# Power.net
KiCad netlist of a schematic drawn in Altium Designer
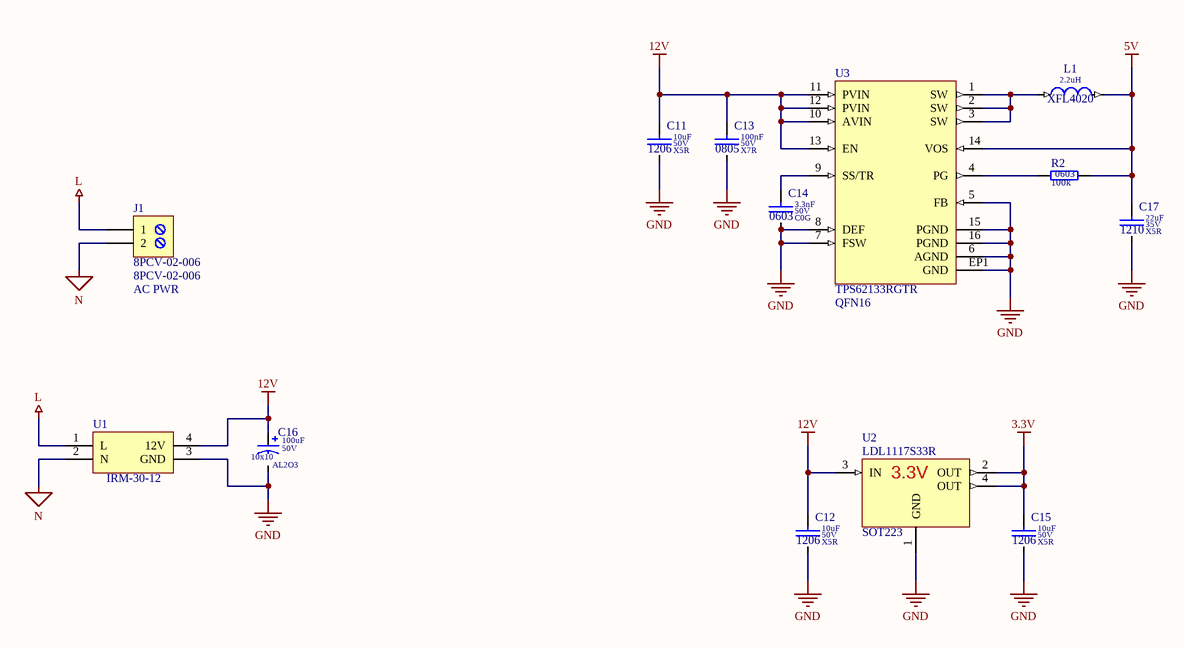
[diagram p0: Power.SchDoc]

(export (version "E")
  (design (tool "Eeschema 10.0.6"))
  (components
    (comp (ref "C11")
      (value "10uF")
      (footprint "C_1206_3216")
      (description "Capacitor")
      (fields
        (field (name "DIELECTRIC") "X5R")
        (field (name "VOLTAGE") "50V")
        (field (name "SCH_FOOTPRINT") "1206")
        (field (name "PART NUMBER") "C_10uF_50V_X5R_1206_10")
        (field (name "MANUFACTURER") "Murata")
      )
      (libsource (lib "Library") (part "C"))
    )
    (comp (ref "C12")
      (value "10uF")
      (footprint "C_1206_3216")
      (description "Capacitor")
      (fields
        (field (name "DIELECTRIC") "X5R")
        (field (name "VOLTAGE") "50V")
        (field (name "SCH_FOOTPRINT") "1206")
        (field (name "PART NUMBER") "C_10uF_50V_X5R_1206_10")
        (field (name "MANUFACTURER") "Murata")
      )
      (libsource (lib "Library") (part "C"))
    )
    (comp (ref "C13")
      (value "100nF")
      (footprint "C_0805_2012")
      (description "Capacitor")
      (fields
        (field (name "DIELECTRIC") "X7R")
        (field (name "VOLTAGE") "50V")
        (field (name "SCH_FOOTPRINT") "0805")
        (field (name "PART NUMBER") "C_100nF_50V_X7R_0805_10")
        (field (name "MANUFACTURER") "AVX")
      )
      (libsource (lib "Library") (part "C"))
    )
    (comp (ref "C14")
      (value "3.3nF")
      (footprint "C_0603_1608")
      (description "Capacitor")
      (fields
        (field (name "DIELECTRIC") "C0G")
        (field (name "VOLTAGE") "50V")
        (field (name "SCH_FOOTPRINT") "0603")
        (field (name "PART NUMBER") "C_3.3nF_50V_C0G_0603_5")
        (field (name "MANUFACTURER") "Murata")
      )
      (libsource (lib "Library") (part "C"))
    )
    (comp (ref "C15")
      (value "10uF")
      (footprint "C_1206_3216")
      (description "Capacitor")
      (fields
        (field (name "DIELECTRIC") "X5R")
        (field (name "VOLTAGE") "50V")
        (field (name "SCH_FOOTPRINT") "1206")
        (field (name "PART NUMBER") "C_10uF_50V_X5R_1206_10")
        (field (name "MANUFACTURER") "Murata")
      )
      (libsource (lib "Library") (part "C"))
    )
    (comp (ref "C16")
      (value "100uF")
      (footprint "CE_D_10x10_SMD")
      (description "Polarized Capacitor")
      (fields
        (field (name "DIELECTRIC") "AL2O3")
        (field (name "SCH_FOOTPRINT") "10x10")
        (field (name "VOLTAGE") "50V")
        (field (name "PART NUMBER") "CE_100uF_50V_AL2O3_10x10_20")
        (field (name "MANUFACTURER") "Nichicon")
      )
      (libsource (lib "Library") (part "CE"))
    )
    (comp (ref "C17")
      (value "22uF")
      (footprint "C_1210_3225")
      (description "Capacitor")
      (fields
        (field (name "DIELECTRIC") "X5R")
        (field (name "VOLTAGE") "35V")
        (field (name "SCH_FOOTPRINT") "1210")
        (field (name "PART NUMBER") "C_22uF_35V_X5R_1210_20")
        (field (name "MANUFACTURER") "Taiyo Yuden")
      )
      (libsource (lib "Library") (part "C"))
    )
    (comp (ref "J1")
      (value "8PCV-02-006")
      (footprint "J_8PCV-02-006")
      (description "ARK Screw terminal, 2-Pin")
      (fields
        (field (name "SCH_FOOTPRINT") "8PCV-02-006")
        (field (name "PART NUMBER") "J_8PCV-02-006")
        (field (name "MANUFACTURER") "TE Connectivity")
      )
      (libsource (lib "Library") (part "J_ARK2"))
    )
    (comp (ref "L1")
      (value "2.2uH")
      (footprint "XFL4020")
      (description "Induction")
      (fields
        (field (name "SCH_FOOTPRINT") "XFL4020")
        (field (name "PART NUMBER") "L_2.2uH_8A_XFL4020")
        (field (name "MANUFACTURER") "Coilcraft")
      )
      (libsource (lib "Library") (part "L"))
    )
    (comp (ref "R2")
      (value "100k")
      (footprint "R_0603_1608")
      (fields
        (field (name "SCH_FOOTPRINT") "0603")
        (field (name "PART NUMBER") "R_100k_0603_1")
        (field (name "VOLTAGE") "50V")
        (field (name "POWER") "100mW")
      )
      (libsource (lib "Library") (part "R"))
    )
    (comp (ref "U1")
      (value "IRM-30-12")
      (footprint "IRM-30-12")
      (description "IRM-30-12 Mean Well")
      (libsource (lib "SchLib") (part "IRM-30-12"))
    )
    (comp (ref "U2")
      (value "LDL1117S33R")
      (footprint "SOT223_SC73")
      (description "typical configuration")
      (fields
        (field (name "SCH_FOOTPRINT") "SOT223")
        (field (name "PART NUMBER") "VL_LDL1117S33R")
        (field (name "VOLTAGE") "3.3V")
      )
      (libsource (lib "Library") (part "VL_4pin_3_1_2,4"))
    )
    (comp (ref "U3")
      (value "TPS62133RGTR")
      (footprint "QFN16_3x3")
      (description "3-17V 3A Step-Down Converter with DCS-Control in 3x3 QFN")
      (fields
        (field (name "SCH_FOOTPRINT") "QFN16")
        (field (name "PART NUMBER") "VS_TPS62133RGTR")
        (field (name "MANUFACTURER") "Texas Instruments")
      )
      (libsource (lib "Library") (part "VS_TPS6213x"))
    )
  )
  (nets
    (net (code "1") (name "3.3V") (class "Default")
      (node (ref "C15") (pin "1") (pinfunction "1_1") (pintype "passive"))
      (node (ref "U2") (pin "2") (pinfunction "OUT_2") (pintype "output"))
      (node (ref "U2") (pin "4") (pinfunction "OUT_4") (pintype "output"))
    )
    (net (code "2") (name "5V") (class "Default")
      (node (ref "C17") (pin "1") (pinfunction "1_1") (pintype "passive"))
      (node (ref "L1") (pin "2") (pinfunction "2_2") (pintype "output"))
      (node (ref "R2") (pin "2") (pinfunction "2_2") (pintype "passive"))
      (node (ref "U3") (pin "14") (pinfunction "VOS_14") (pintype "input"))
    )
    (net (code "3") (name "12V") (class "Default")
      (node (ref "C11") (pin "1") (pinfunction "1_1") (pintype "passive"))
      (node (ref "C12") (pin "1") (pinfunction "1_1") (pintype "passive"))
      (node (ref "C13") (pin "1") (pinfunction "1_1") (pintype "passive"))
      (node (ref "C16") (pin "1") (pinfunction "1_1") (pintype "passive"))
      (node (ref "U1") (pin "4") (pinfunction "12V_4") (pintype "passive"))
      (node (ref "U2") (pin "3") (pinfunction "IN_3") (pintype "input"))
      (node (ref "U3") (pin "10") (pinfunction "AVIN_10") (pintype "input"))
      (node (ref "U3") (pin "11") (pinfunction "PVIN_11") (pintype "input"))
      (node (ref "U3") (pin "12") (pinfunction "PVIN_12") (pintype "input"))
      (node (ref "U3") (pin "13") (pinfunction "EN_13") (pintype "input"))
    )
    (net (code "4") (name "GND") (class "Default")
      (node (ref "C11") (pin "2") (pinfunction "2_2") (pintype "passive"))
      (node (ref "C12") (pin "2") (pinfunction "2_2") (pintype "passive"))
      (node (ref "C13") (pin "2") (pinfunction "2_2") (pintype "passive"))
      (node (ref "C14") (pin "2") (pinfunction "2_2") (pintype "passive"))
      (node (ref "C15") (pin "2") (pinfunction "2_2") (pintype "passive"))
      (node (ref "C16") (pin "2") (pinfunction "2_2") (pintype "passive"))
      (node (ref "C17") (pin "2") (pinfunction "2_2") (pintype "passive"))
      (node (ref "U1") (pin "3") (pinfunction "GND_3") (pintype "passive"))
      (node (ref "U2") (pin "1") (pinfunction "GND_1") (pintype "power_in"))
      (node (ref "U3") (pin "15") (pinfunction "PGND_15") (pintype "power_in"))
      (node (ref "U3") (pin "16") (pinfunction "PGND_16") (pintype "power_in"))
      (node (ref "U3") (pin "5") (pinfunction "FB_5") (pintype "input"))
      (node (ref "U3") (pin "6") (pinfunction "AGND_6") (pintype "power_in"))
      (node (ref "U3") (pin "7") (pinfunction "FSW_7") (pintype "input"))
      (node (ref "U3") (pin "8") (pinfunction "DEF_8") (pintype "input"))
      (node (ref "U3") (pin "EP1") (pinfunction "GND_EP1") (pintype "power_in"))
    )
    (net (code "5") (name "L") (class "Default")
      (node (ref "J1") (pin "1") (pinfunction "1_1") (pintype "passive"))
      (node (ref "U1") (pin "1") (pinfunction "L_1") (pintype "passive"))
    )
    (net (code "6") (name "N") (class "Default")
      (node (ref "J1") (pin "2") (pinfunction "2_2") (pintype "passive"))
      (node (ref "U1") (pin "2") (pinfunction "N_2") (pintype "passive"))
    )
    (net (code "7") (name "Net-(L1-Pad1)") (class "Default")
      (node (ref "L1") (pin "1") (pinfunction "1_1") (pintype "input"))
      (node (ref "U3") (pin "1") (pinfunction "SW_1") (pintype "output"))
      (node (ref "U3") (pin "2") (pinfunction "SW_2") (pintype "output"))
      (node (ref "U3") (pin "3") (pinfunction "SW_3") (pintype "output"))
    )
    (net (code "8") (name "Net-(U3-PG)") (class "Default")
      (node (ref "R2") (pin "1") (pinfunction "1_1") (pintype "passive"))
      (node (ref "U3") (pin "4") (pinfunction "PG_4") (pintype "output"))
    )
    (net (code "9") (name "Net-(U3-SS{slash}TR)") (class "Default")
      (node (ref "C14") (pin "1") (pinfunction "1_1") (pintype "passive"))
      (node (ref "U3") (pin "9") (pinfunction "SS/TR_9") (pintype "input"))
    )
  )
)
